# star-tracker-camera-breakout.net
KiCad netlist of a schematic drawn in EAGLE
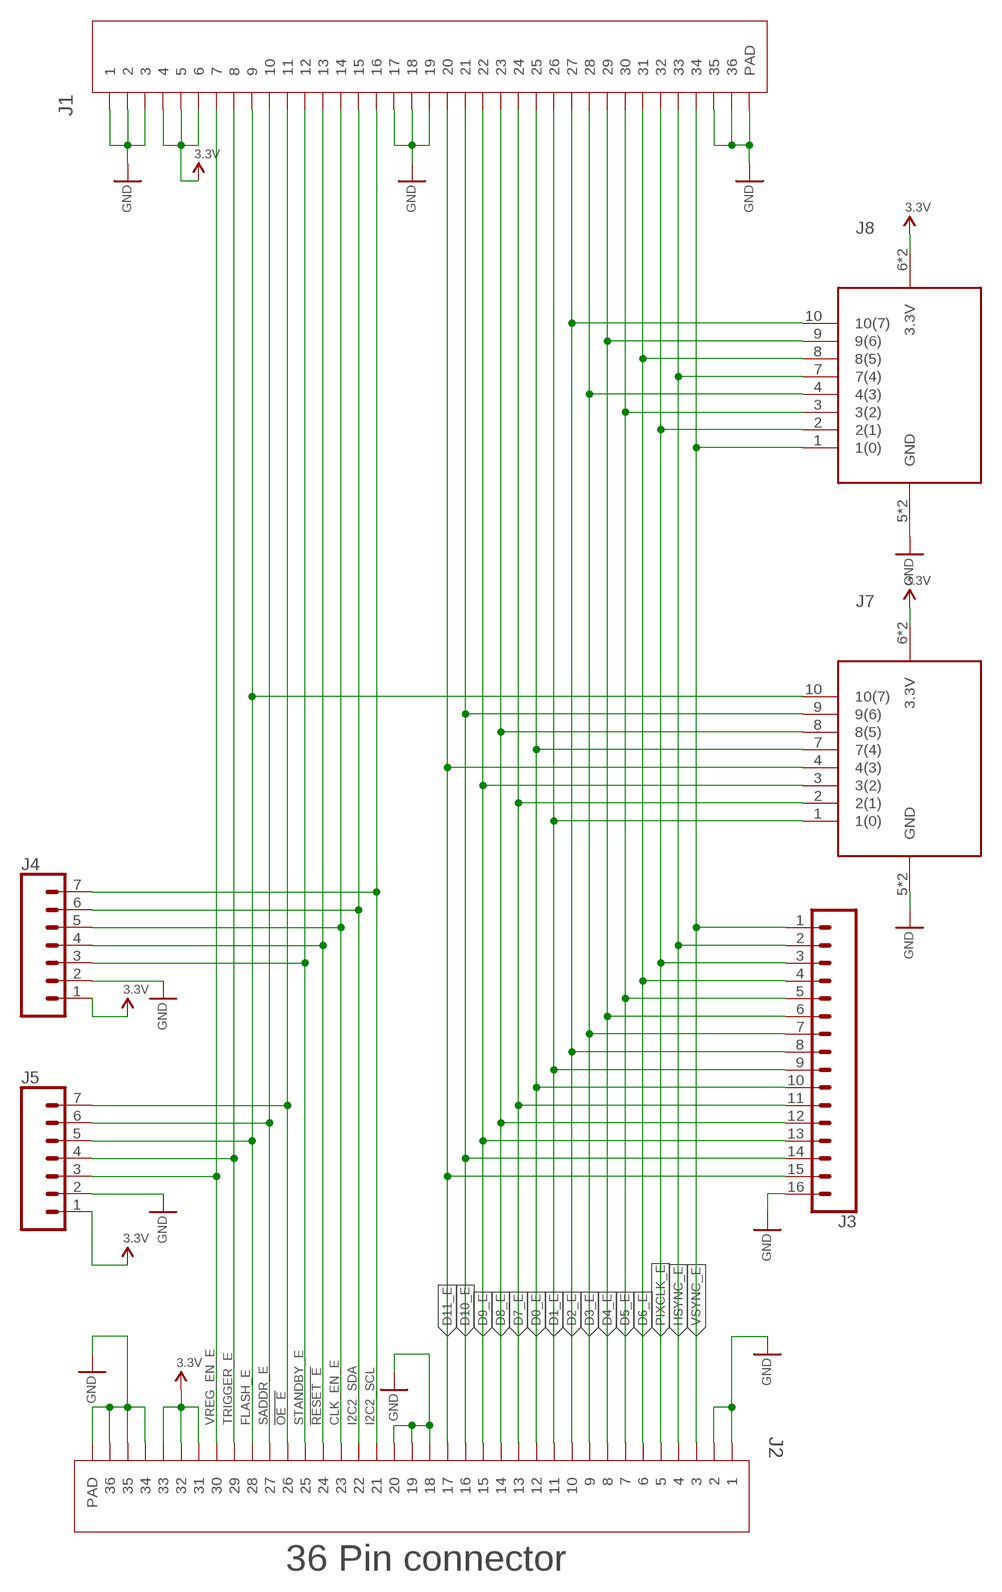
[diagram p0: schematic, sheet 1]

(export (version "E")
  (design (tool "Eeschema 10.0.6"))
  (components
    (comp (ref "J1")
      (value "3-1734592-64-1734592-0")
      (footprint "eagle-import:TE_3-1734592-6")
      (fields (field (name "MPN") "3-1734592-6"))
      (libsource (lib "eagle-import") (part "3-1734592-64-1734592-0"))
    )
    (comp (ref "J2")
      (value "3-1734592-64-1734592-0")
      (footprint "eagle-import:TE_3-1734592-6")
      (fields (field (name "MPN") "3-1734592-6"))
      (libsource (lib "eagle-import") (part "3-1734592-64-1734592-0"))
    )
    (comp (ref "J3")
      (value "CONN_16")
      (footprint "eagle-import:1X16")
      (libsource (lib "eagle-import") (part "CONN_16"))
    )
    (comp (ref "J4")
      (value "CONN_07")
      (footprint "eagle-import:1X07")
      (libsource (lib "eagle-import") (part "CONN_07"))
    )
    (comp (ref "J5")
      (value "CONN_07")
      (footprint "eagle-import:1X07")
      (libsource (lib "eagle-import") (part "CONN_07"))
    )
    (comp (ref "J7")
      (value "2X6 FEMALE")
      (footprint "eagle-import:PMOD_PERIPH")
      (libsource (lib "eagle-import") (part "PMOD_PERIPHPTH_FEMALE"))
    )
    (comp (ref "J8")
      (value "2X6 FEMALE")
      (footprint "eagle-import:PMOD_PERIPH")
      (libsource (lib "eagle-import") (part "PMOD_PERIPHPTH_FEMALE"))
    )
  )
  (nets
    (net (code "1") (name "/CLK_EN_E") (class "Default")
      (node (ref "J1") (pin "14") (pinfunction "14_14") (pintype "passive"))
      (node (ref "J2") (pin "23") (pinfunction "23_23") (pintype "passive"))
      (node (ref "J4") (pin "5") (pinfunction "5_5") (pintype "passive"))
    )
    (net (code "2") (name "/FLASH_E") (class "Default")
      (node (ref "J1") (pin "9") (pinfunction "9_9") (pintype "passive"))
      (node (ref "J2") (pin "28") (pinfunction "28_28") (pintype "passive"))
      (node (ref "J5") (pin "5") (pinfunction "5_5") (pintype "passive"))
      (node (ref "J7") (pin "10") (pinfunction "10(7)_10") (pintype "bidirectional"))
    )
    (net (code "3") (name "/I2C2_SCL") (class "Default")
      (node (ref "J1") (pin "16") (pinfunction "16_16") (pintype "passive"))
      (node (ref "J2") (pin "21") (pinfunction "21_21") (pintype "passive"))
      (node (ref "J4") (pin "7") (pinfunction "7_7") (pintype "passive"))
    )
    (net (code "4") (name "/I2C2_SDA") (class "Default")
      (node (ref "J1") (pin "15") (pinfunction "15_15") (pintype "passive"))
      (node (ref "J2") (pin "22") (pinfunction "22_22") (pintype "passive"))
      (node (ref "J4") (pin "6") (pinfunction "6_6") (pintype "passive"))
    )
    (net (code "5") (name "/SADDR_E") (class "Default")
      (node (ref "J1") (pin "10") (pinfunction "10_10") (pintype "passive"))
      (node (ref "J2") (pin "27") (pinfunction "27_27") (pintype "passive"))
      (node (ref "J5") (pin "6") (pinfunction "6_6") (pintype "passive"))
    )
    (net (code "6") (name "/STANDBY_E") (class "Default")
      (node (ref "J1") (pin "12") (pinfunction "12_12") (pintype "passive"))
      (node (ref "J2") (pin "25") (pinfunction "25_25") (pintype "passive"))
      (node (ref "J4") (pin "3") (pinfunction "3_3") (pintype "passive"))
    )
    (net (code "7") (name "/TRIGGER_E") (class "Default")
      (node (ref "J1") (pin "8") (pinfunction "8_8") (pintype "passive"))
      (node (ref "J2") (pin "29") (pinfunction "29_29") (pintype "passive"))
      (node (ref "J5") (pin "4") (pinfunction "4_4") (pintype "passive"))
    )
    (net (code "8") (name "/VREG_EN_E") (class "Default")
      (node (ref "J1") (pin "7") (pinfunction "7_7") (pintype "passive"))
      (node (ref "J2") (pin "30") (pinfunction "30_30") (pintype "passive"))
      (node (ref "J5") (pin "3") (pinfunction "3_3") (pintype "passive"))
    )
    (net (code "9") (name "/~{OE_E}") (class "Default")
      (node (ref "J1") (pin "11") (pinfunction "11_11") (pintype "passive"))
      (node (ref "J2") (pin "26") (pinfunction "26_26") (pintype "passive"))
      (node (ref "J5") (pin "7") (pinfunction "7_7") (pintype "passive"))
    )
    (net (code "10") (name "/~{RESET_E}") (class "Default")
      (node (ref "J1") (pin "13") (pinfunction "13_13") (pintype "passive"))
      (node (ref "J2") (pin "24") (pinfunction "24_24") (pintype "passive"))
      (node (ref "J4") (pin "4") (pinfunction "4_4") (pintype "passive"))
    )
    (net (code "11") (name "3.3V") (class "Default")
      (node (ref "J1") (pin "4") (pinfunction "4_4") (pintype "passive"))
      (node (ref "J1") (pin "5") (pinfunction "5_5") (pintype "passive"))
      (node (ref "J1") (pin "6") (pinfunction "6_6") (pintype "passive"))
      (node (ref "J2") (pin "31") (pinfunction "31_31") (pintype "passive"))
      (node (ref "J2") (pin "32") (pinfunction "32_32") (pintype "passive"))
      (node (ref "J2") (pin "33") (pinfunction "33_33") (pintype "passive"))
      (node (ref "J4") (pin "1") (pinfunction "1_1") (pintype "passive"))
      (node (ref "J5") (pin "1") (pinfunction "1_1") (pintype "passive"))
      (node (ref "J7") (pin "12") (pinfunction "3.3V_12") (pintype "bidirectional"))
      (node (ref "J7") (pin "6") (pinfunction "3.3V_6") (pintype "bidirectional"))
      (node (ref "J8") (pin "12") (pinfunction "3.3V_12") (pintype "bidirectional"))
      (node (ref "J8") (pin "6") (pinfunction "3.3V_6") (pintype "bidirectional"))
    )
    (net (code "12") (name "D0_E") (class "Default")
      (node (ref "J1") (pin "25") (pinfunction "25_25") (pintype "passive"))
      (node (ref "J2") (pin "12") (pinfunction "12_12") (pintype "passive"))
      (node (ref "J3") (pin "10") (pinfunction "10_10") (pintype "passive"))
      (node (ref "J7") (pin "7") (pinfunction "7(4)_7") (pintype "bidirectional"))
    )
    (net (code "13") (name "D1_E") (class "Default")
      (node (ref "J1") (pin "26") (pinfunction "26_26") (pintype "passive"))
      (node (ref "J2") (pin "11") (pinfunction "11_11") (pintype "passive"))
      (node (ref "J3") (pin "9") (pinfunction "9_9") (pintype "passive"))
      (node (ref "J7") (pin "1") (pinfunction "1(0)_1") (pintype "bidirectional"))
    )
    (net (code "14") (name "D2_E") (class "Default")
      (node (ref "J1") (pin "27") (pinfunction "27_27") (pintype "passive"))
      (node (ref "J2") (pin "10") (pinfunction "10_10") (pintype "passive"))
      (node (ref "J3") (pin "8") (pinfunction "8_8") (pintype "passive"))
      (node (ref "J8") (pin "10") (pinfunction "10(7)_10") (pintype "bidirectional"))
    )
    (net (code "15") (name "D3_E") (class "Default")
      (node (ref "J1") (pin "28") (pinfunction "28_28") (pintype "passive"))
      (node (ref "J2") (pin "9") (pinfunction "9_9") (pintype "passive"))
      (node (ref "J3") (pin "7") (pinfunction "7_7") (pintype "passive"))
      (node (ref "J8") (pin "4") (pinfunction "4(3)_4") (pintype "bidirectional"))
    )
    (net (code "16") (name "D4_E") (class "Default")
      (node (ref "J1") (pin "29") (pinfunction "29_29") (pintype "passive"))
      (node (ref "J2") (pin "8") (pinfunction "8_8") (pintype "passive"))
      (node (ref "J3") (pin "6") (pinfunction "6_6") (pintype "passive"))
      (node (ref "J8") (pin "9") (pinfunction "9(6)_9") (pintype "bidirectional"))
    )
    (net (code "17") (name "D5_E") (class "Default")
      (node (ref "J1") (pin "30") (pinfunction "30_30") (pintype "passive"))
      (node (ref "J2") (pin "7") (pinfunction "7_7") (pintype "passive"))
      (node (ref "J3") (pin "5") (pinfunction "5_5") (pintype "passive"))
      (node (ref "J8") (pin "3") (pinfunction "3(2)_3") (pintype "bidirectional"))
    )
    (net (code "18") (name "D6_E") (class "Default")
      (node (ref "J1") (pin "31") (pinfunction "31_31") (pintype "passive"))
      (node (ref "J2") (pin "6") (pinfunction "6_6") (pintype "passive"))
      (node (ref "J3") (pin "4") (pinfunction "4_4") (pintype "passive"))
      (node (ref "J8") (pin "8") (pinfunction "8(5)_8") (pintype "bidirectional"))
    )
    (net (code "19") (name "D7_E") (class "Default")
      (node (ref "J1") (pin "24") (pinfunction "24_24") (pintype "passive"))
      (node (ref "J2") (pin "13") (pinfunction "13_13") (pintype "passive"))
      (node (ref "J3") (pin "11") (pinfunction "11_11") (pintype "passive"))
      (node (ref "J7") (pin "2") (pinfunction "2(1)_2") (pintype "bidirectional"))
    )
    (net (code "20") (name "D8_E") (class "Default")
      (node (ref "J1") (pin "23") (pinfunction "23_23") (pintype "passive"))
      (node (ref "J2") (pin "14") (pinfunction "14_14") (pintype "passive"))
      (node (ref "J3") (pin "12") (pinfunction "12_12") (pintype "passive"))
      (node (ref "J7") (pin "8") (pinfunction "8(5)_8") (pintype "bidirectional"))
    )
    (net (code "21") (name "D9_E") (class "Default")
      (node (ref "J1") (pin "22") (pinfunction "22_22") (pintype "passive"))
      (node (ref "J2") (pin "15") (pinfunction "15_15") (pintype "passive"))
      (node (ref "J3") (pin "13") (pinfunction "13_13") (pintype "passive"))
      (node (ref "J7") (pin "3") (pinfunction "3(2)_3") (pintype "bidirectional"))
    )
    (net (code "22") (name "D10_E") (class "Default")
      (node (ref "J1") (pin "21") (pinfunction "21_21") (pintype "passive"))
      (node (ref "J2") (pin "16") (pinfunction "16_16") (pintype "passive"))
      (node (ref "J3") (pin "14") (pinfunction "14_14") (pintype "passive"))
      (node (ref "J7") (pin "9") (pinfunction "9(6)_9") (pintype "bidirectional"))
    )
    (net (code "23") (name "D11_E") (class "Default")
      (node (ref "J1") (pin "20") (pinfunction "20_20") (pintype "passive"))
      (node (ref "J2") (pin "17") (pinfunction "17_17") (pintype "passive"))
      (node (ref "J3") (pin "15") (pinfunction "15_15") (pintype "passive"))
      (node (ref "J7") (pin "4") (pinfunction "4(3)_4") (pintype "bidirectional"))
    )
    (net (code "24") (name "GND") (class "Default")
      (node (ref "J1") (pin "1") (pinfunction "1_1") (pintype "passive"))
      (node (ref "J1") (pin "17") (pinfunction "17_17") (pintype "passive"))
      (node (ref "J1") (pin "18") (pinfunction "18_18") (pintype "passive"))
      (node (ref "J1") (pin "19") (pinfunction "19_19") (pintype "passive"))
      (node (ref "J1") (pin "2") (pinfunction "2_2") (pintype "passive"))
      (node (ref "J1") (pin "3") (pinfunction "3_3") (pintype "passive"))
      (node (ref "J1") (pin "35") (pinfunction "35_35") (pintype "passive"))
      (node (ref "J1") (pin "36") (pinfunction "36_36") (pintype "passive"))
      (node (ref "J1") (pin "S1") (pinfunction "PAD_S1") (pintype "bidirectional"))
      (node (ref "J1") (pin "S2") (pinfunction "PAD_S2") (pintype "bidirectional"))
      (node (ref "J2") (pin "1") (pinfunction "1_1") (pintype "passive"))
      (node (ref "J2") (pin "18") (pinfunction "18_18") (pintype "passive"))
      (node (ref "J2") (pin "19") (pinfunction "19_19") (pintype "passive"))
      (node (ref "J2") (pin "2") (pinfunction "2_2") (pintype "passive"))
      (node (ref "J2") (pin "20") (pinfunction "20_20") (pintype "passive"))
      (node (ref "J2") (pin "34") (pinfunction "34_34") (pintype "passive"))
      (node (ref "J2") (pin "35") (pinfunction "35_35") (pintype "passive"))
      (node (ref "J2") (pin "36") (pinfunction "36_36") (pintype "passive"))
      (node (ref "J2") (pin "S1") (pinfunction "PAD_S1") (pintype "bidirectional"))
      (node (ref "J2") (pin "S2") (pinfunction "PAD_S2") (pintype "bidirectional"))
      (node (ref "J3") (pin "16") (pinfunction "16_16") (pintype "passive"))
      (node (ref "J4") (pin "2") (pinfunction "2_2") (pintype "passive"))
      (node (ref "J5") (pin "2") (pinfunction "2_2") (pintype "passive"))
      (node (ref "J7") (pin "11") (pinfunction "GND_11") (pintype "bidirectional"))
      (node (ref "J7") (pin "5") (pinfunction "GND_5") (pintype "bidirectional"))
      (node (ref "J8") (pin "11") (pinfunction "GND_11") (pintype "bidirectional"))
      (node (ref "J8") (pin "5") (pinfunction "GND_5") (pintype "bidirectional"))
    )
    (net (code "25") (name "HSYNC_E") (class "Default")
      (node (ref "J1") (pin "33") (pinfunction "33_33") (pintype "passive"))
      (node (ref "J2") (pin "4") (pinfunction "4_4") (pintype "passive"))
      (node (ref "J3") (pin "2") (pinfunction "2_2") (pintype "passive"))
      (node (ref "J8") (pin "7") (pinfunction "7(4)_7") (pintype "bidirectional"))
    )
    (net (code "26") (name "PIXCLK_E") (class "Default")
      (node (ref "J1") (pin "32") (pinfunction "32_32") (pintype "passive"))
      (node (ref "J2") (pin "5") (pinfunction "5_5") (pintype "passive"))
      (node (ref "J3") (pin "3") (pinfunction "3_3") (pintype "passive"))
      (node (ref "J8") (pin "2") (pinfunction "2(1)_2") (pintype "bidirectional"))
    )
    (net (code "27") (name "VSYNC_E") (class "Default")
      (node (ref "J1") (pin "34") (pinfunction "34_34") (pintype "passive"))
      (node (ref "J2") (pin "3") (pinfunction "3_3") (pintype "passive"))
      (node (ref "J3") (pin "1") (pinfunction "1_1") (pintype "passive"))
      (node (ref "J8") (pin "1") (pinfunction "1(0)_1") (pintype "bidirectional"))
    )
  )
)
